# BuSPIrate_breakout.net
KiCad netlist of a schematic drawn in EAGLE
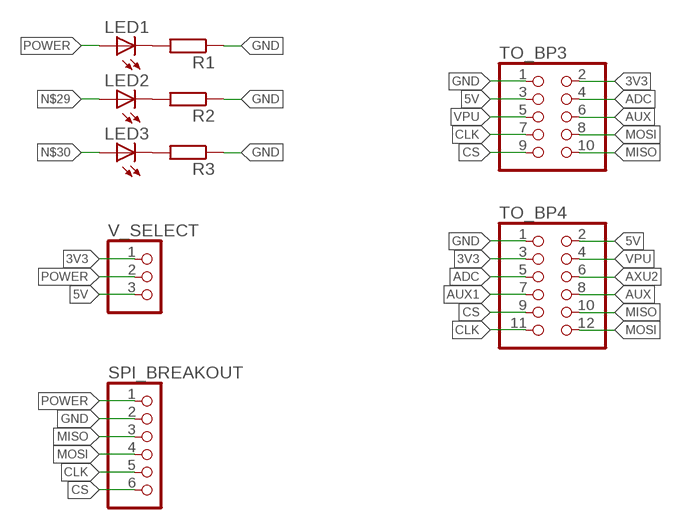
[diagram p0: schematic, sheet 1]

(export (version "E")
  (design (tool "Eeschema 10.0.6"))
  (components
    (comp (ref "LED1")
      (value "LEDSML1206")
      (footprint "eagle-import:SML1206")
      (libsource (lib "eagle-import") (part "LEDSML1206"))
    )
    (comp (ref "LED2")
      (value "LEDSML1206")
      (footprint "eagle-import:SML1206")
      (libsource (lib "eagle-import") (part "LEDSML1206"))
    )
    (comp (ref "LED3")
      (value "LEDSML1206")
      (footprint "eagle-import:SML1206")
      (libsource (lib "eagle-import") (part "LEDSML1206"))
    )
    (comp (ref "R1")
      (value "R-EU_M1206")
      (footprint "eagle-import:M1206")
      (libsource (lib "eagle-import") (part "R-EU_M1206"))
    )
    (comp (ref "R2")
      (value "R-EU_M1206")
      (footprint "eagle-import:M1206")
      (libsource (lib "eagle-import") (part "R-EU_M1206"))
    )
    (comp (ref "R3")
      (value "R-EU_M1206")
      (footprint "eagle-import:M1206")
      (libsource (lib "eagle-import") (part "R-EU_M1206"))
    )
    (comp (ref "SPI_BREAKOUT")
      (value "PINHD-1X6")
      (footprint "eagle-import:1X06")
      (libsource (lib "eagle-import") (part "PINHD-1X6"))
    )
    (comp (ref "TO_BP3")
      (value "PINHD-2X5")
      (footprint "eagle-import:2X05")
      (libsource (lib "eagle-import") (part "PINHD-2X5"))
    )
    (comp (ref "TO_BP4")
      (value "PINHD-2X6")
      (footprint "eagle-import:2X06")
      (libsource (lib "eagle-import") (part "PINHD-2X6"))
    )
    (comp (ref "V_SELECT")
      (value "PINHD-1X3")
      (footprint "eagle-import:1X03")
      (libsource (lib "eagle-import") (part "PINHD-1X3"))
    )
  )
  (nets
    (net (code "1") (name "3V3") (class "Default")
      (node (ref "TO_BP3") (pin "2") (pinfunction "2_2") (pintype "passive"))
      (node (ref "TO_BP4") (pin "3") (pinfunction "3_3") (pintype "passive"))
      (node (ref "V_SELECT") (pin "1") (pinfunction "1_1") (pintype "passive"))
    )
    (net (code "2") (name "5V") (class "Default")
      (node (ref "TO_BP3") (pin "3") (pinfunction "3_3") (pintype "passive"))
      (node (ref "TO_BP4") (pin "2") (pinfunction "2_2") (pintype "passive"))
      (node (ref "V_SELECT") (pin "3") (pinfunction "3_3") (pintype "passive"))
    )
    (net (code "3") (name "ADC") (class "Default")
      (node (ref "TO_BP3") (pin "4") (pinfunction "4_4") (pintype "passive"))
      (node (ref "TO_BP4") (pin "5") (pinfunction "5_5") (pintype "passive"))
    )
    (net (code "4") (name "AUX") (class "Default")
      (node (ref "TO_BP3") (pin "6") (pinfunction "6_6") (pintype "passive"))
      (node (ref "TO_BP4") (pin "8") (pinfunction "8_8") (pintype "passive"))
    )
    (net (code "5") (name "AUX1") (class "Default")
      (node (ref "TO_BP4") (pin "7") (pinfunction "7_7") (pintype "passive"))
    )
    (net (code "6") (name "AXU2") (class "Default")
      (node (ref "TO_BP4") (pin "6") (pinfunction "6_6") (pintype "passive"))
    )
    (net (code "7") (name "CLK") (class "Default")
      (node (ref "SPI_BREAKOUT") (pin "5") (pinfunction "5_5") (pintype "passive"))
      (node (ref "TO_BP3") (pin "7") (pinfunction "7_7") (pintype "passive"))
      (node (ref "TO_BP4") (pin "11") (pinfunction "11_11") (pintype "passive"))
    )
    (net (code "8") (name "CS") (class "Default")
      (node (ref "SPI_BREAKOUT") (pin "6") (pinfunction "6_6") (pintype "passive"))
      (node (ref "TO_BP3") (pin "9") (pinfunction "9_9") (pintype "passive"))
      (node (ref "TO_BP4") (pin "9") (pinfunction "9_9") (pintype "passive"))
    )
    (net (code "9") (name "GND") (class "Default")
      (node (ref "R1") (pin "1") (pinfunction "1_1") (pintype "passive"))
      (node (ref "R2") (pin "1") (pinfunction "1_1") (pintype "passive"))
      (node (ref "R3") (pin "1") (pinfunction "1_1") (pintype "passive"))
      (node (ref "SPI_BREAKOUT") (pin "2") (pinfunction "2_2") (pintype "passive"))
      (node (ref "TO_BP3") (pin "1") (pinfunction "1_1") (pintype "passive"))
      (node (ref "TO_BP4") (pin "1") (pinfunction "1_1") (pintype "passive"))
    )
    (net (code "10") (name "MISO") (class "Default")
      (node (ref "SPI_BREAKOUT") (pin "3") (pinfunction "3_3") (pintype "passive"))
      (node (ref "TO_BP3") (pin "10") (pinfunction "10_10") (pintype "passive"))
      (node (ref "TO_BP4") (pin "10") (pinfunction "10_10") (pintype "passive"))
    )
    (net (code "11") (name "MOSI") (class "Default")
      (node (ref "SPI_BREAKOUT") (pin "4") (pinfunction "4_4") (pintype "passive"))
      (node (ref "TO_BP3") (pin "8") (pinfunction "8_8") (pintype "passive"))
      (node (ref "TO_BP4") (pin "12") (pinfunction "12_12") (pintype "passive"))
    )
    (net (code "12") (name "N$29") (class "Default")
      (node (ref "LED2") (pin "A") (pinfunction "A_A") (pintype "passive"))
    )
    (net (code "13") (name "N$30") (class "Default")
      (node (ref "LED3") (pin "A") (pinfunction "A_A") (pintype "passive"))
    )
    (net (code "14") (name "Net-(LED1-PadC)") (class "Default")
      (node (ref "LED1") (pin "C") (pinfunction "C_C") (pintype "passive"))
      (node (ref "R1") (pin "2") (pinfunction "2_2") (pintype "passive"))
    )
    (net (code "15") (name "Net-(LED2-PadC)") (class "Default")
      (node (ref "LED2") (pin "C") (pinfunction "C_C") (pintype "passive"))
      (node (ref "R2") (pin "2") (pinfunction "2_2") (pintype "passive"))
    )
    (net (code "16") (name "Net-(LED3-PadC)") (class "Default")
      (node (ref "LED3") (pin "C") (pinfunction "C_C") (pintype "passive"))
      (node (ref "R3") (pin "2") (pinfunction "2_2") (pintype "passive"))
    )
    (net (code "17") (name "POWER") (class "Default")
      (node (ref "LED1") (pin "A") (pinfunction "A_A") (pintype "passive"))
      (node (ref "SPI_BREAKOUT") (pin "1") (pinfunction "1_1") (pintype "passive"))
      (node (ref "V_SELECT") (pin "2") (pinfunction "2_2") (pintype "passive"))
    )
    (net (code "18") (name "VPU") (class "Default")
      (node (ref "TO_BP3") (pin "5") (pinfunction "5_5") (pintype "passive"))
      (node (ref "TO_BP4") (pin "4") (pinfunction "4_4") (pintype "passive"))
    )
  )
)
